# fp1.net
KiCad netlist of a schematic drawn in EAGLE
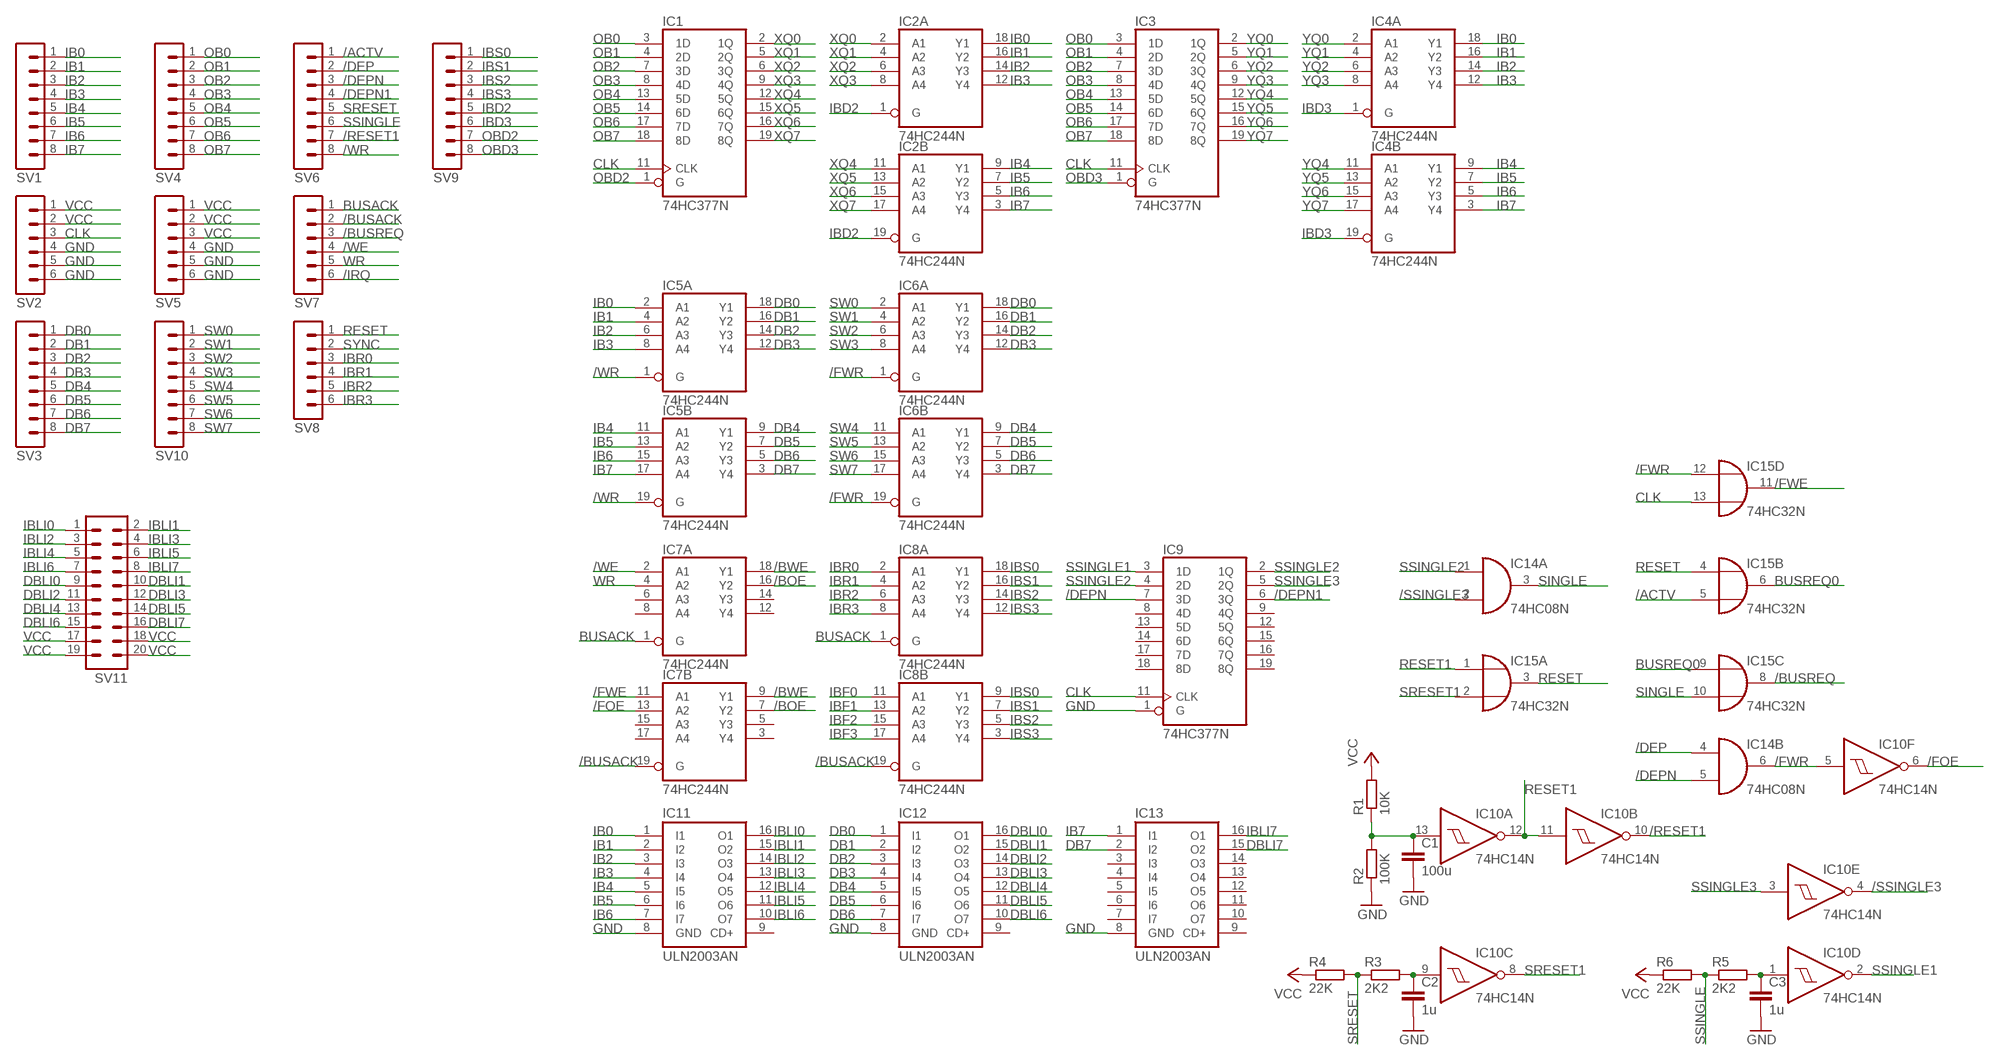
[diagram p0: schematic, sheet 1]

(export (version "E")
  (design (tool "Eeschema 10.0.6"))
  (components
    (comp (ref "C1")
      (value "100u")
      (footprint "eagle-import:C025-024X044")
      (libsource (lib "eagle-import") (part "C-EU025-024X044"))
    )
    (comp (ref "C2")
      (value "1u")
      (footprint "eagle-import:C025-024X044")
      (libsource (lib "eagle-import") (part "C-EU025-024X044"))
    )
    (comp (ref "C3")
      (value "1u")
      (footprint "eagle-import:C025-024X044")
      (libsource (lib "eagle-import") (part "C-EU025-024X044"))
    )
    (comp (ref "IC1")
      (value "74HC377N")
      (footprint "eagle-import:DIL20")
      (libsource (lib "eagle-import") (part "74377NHC"))
    )
    (comp (ref "IC2")
      (value "74HC244N")
      (footprint "eagle-import:DIL20")
      (libsource (lib "eagle-import") (part "74244NHC"))
    )
    (comp (ref "IC3")
      (value "74HC377N")
      (footprint "eagle-import:DIL20")
      (libsource (lib "eagle-import") (part "74377NHC"))
    )
    (comp (ref "IC4")
      (value "74HC244N")
      (footprint "eagle-import:DIL20")
      (libsource (lib "eagle-import") (part "74244NHC"))
    )
    (comp (ref "IC5")
      (value "74HC244N")
      (footprint "eagle-import:DIL20")
      (libsource (lib "eagle-import") (part "74244NHC"))
    )
    (comp (ref "IC6")
      (value "74HC244N")
      (footprint "eagle-import:DIL20")
      (libsource (lib "eagle-import") (part "74244NHC"))
    )
    (comp (ref "IC7")
      (value "74HC244N")
      (footprint "eagle-import:DIL20")
      (libsource (lib "eagle-import") (part "74244NHC"))
    )
    (comp (ref "IC8")
      (value "74HC244N")
      (footprint "eagle-import:DIL20")
      (libsource (lib "eagle-import") (part "74244NHC"))
    )
    (comp (ref "IC9")
      (value "74HC377N")
      (footprint "eagle-import:DIL20")
      (libsource (lib "eagle-import") (part "74377NHC"))
    )
    (comp (ref "IC10")
      (value "74HC14N")
      (footprint "eagle-import:DIL14")
      (libsource (lib "eagle-import") (part "7414NHC"))
    )
    (comp (ref "IC11")
      (value "ULN2003AN")
      (footprint "eagle-import:DIL16")
      (libsource (lib "eagle-import") (part "ULN2003AN"))
    )
    (comp (ref "IC12")
      (value "ULN2003AN")
      (footprint "eagle-import:DIL16")
      (libsource (lib "eagle-import") (part "ULN2003AN"))
    )
    (comp (ref "IC13")
      (value "ULN2003AN")
      (footprint "eagle-import:DIL16")
      (libsource (lib "eagle-import") (part "ULN2003AN"))
    )
    (comp (ref "IC14")
      (value "74HC08N")
      (footprint "eagle-import:DIL14")
      (libsource (lib "eagle-import") (part "7408NHC"))
    )
    (comp (ref "IC15")
      (value "74HC32N")
      (footprint "eagle-import:DIL14")
      (libsource (lib "eagle-import") (part "7432NHC"))
    )
    (comp (ref "R1")
      (value "10K")
      (footprint "eagle-import:0207_7")
      (libsource (lib "eagle-import") (part "R-EU_0207/7"))
    )
    (comp (ref "R2")
      (value "100K")
      (footprint "eagle-import:0207_7")
      (libsource (lib "eagle-import") (part "R-EU_0207/7"))
    )
    (comp (ref "R3")
      (value "2K2")
      (footprint "eagle-import:0207_7")
      (libsource (lib "eagle-import") (part "R-EU_0207/7"))
    )
    (comp (ref "R4")
      (value "22K")
      (footprint "eagle-import:0207_7")
      (libsource (lib "eagle-import") (part "R-EU_0207/7"))
    )
    (comp (ref "R5")
      (value "2K2")
      (footprint "eagle-import:0207_7")
      (libsource (lib "eagle-import") (part "R-EU_0207/7"))
    )
    (comp (ref "R6")
      (value "22K")
      (footprint "eagle-import:0207_7")
      (libsource (lib "eagle-import") (part "R-EU_0207/7"))
    )
    (comp (ref "SV1")
      (value "MA08-1")
      (footprint "eagle-import:MA08-1")
      (libsource (lib "eagle-import") (part "MA08-1"))
    )
    (comp (ref "SV2")
      (value "MA06-1")
      (footprint "eagle-import:MA06-1")
      (libsource (lib "eagle-import") (part "MA06-1"))
    )
    (comp (ref "SV3")
      (value "MA08-1")
      (footprint "eagle-import:MA08-1")
      (libsource (lib "eagle-import") (part "MA08-1"))
    )
    (comp (ref "SV4")
      (value "MA08-1")
      (footprint "eagle-import:MA08-1")
      (libsource (lib "eagle-import") (part "MA08-1"))
    )
    (comp (ref "SV5")
      (value "MA06-1")
      (footprint "eagle-import:MA06-1")
      (libsource (lib "eagle-import") (part "MA06-1"))
    )
    (comp (ref "SV6")
      (value "MA08-1")
      (footprint "eagle-import:MA08-1")
      (libsource (lib "eagle-import") (part "MA08-1"))
    )
    (comp (ref "SV7")
      (value "MA06-1")
      (footprint "eagle-import:MA06-1")
      (libsource (lib "eagle-import") (part "MA06-1"))
    )
    (comp (ref "SV8")
      (value "MA06-1")
      (footprint "eagle-import:MA06-1")
      (libsource (lib "eagle-import") (part "MA06-1"))
    )
    (comp (ref "SV9")
      (value "MA08-1")
      (footprint "eagle-import:MA08-1")
      (libsource (lib "eagle-import") (part "MA08-1"))
    )
    (comp (ref "SV10")
      (value "MA08-1")
      (footprint "eagle-import:MA08-1")
      (libsource (lib "eagle-import") (part "MA08-1"))
    )
    (comp (ref "SV11")
      (value "MA10-2")
      (footprint "eagle-import:MA10-2")
      (libsource (lib "eagle-import") (part "MA10-2"))
    )
  )
  (nets
    (net (code "1") (name "/BUSACK") (class "Default")
      (node (ref "IC7") (pin "1") (pinfunction "G_1") (pintype "input"))
      (node (ref "IC8") (pin "1") (pinfunction "G_1") (pintype "input"))
      (node (ref "SV7") (pin "1") (pinfunction "1_1") (pintype "passive"))
    )
    (net (code "2") (name "/BUSREQ0") (class "Default")
      (node (ref "IC15") (pin "6") (pinfunction "O_6") (pintype "output"))
      (node (ref "IC15") (pin "9") (pinfunction "I0_9") (pintype "input"))
    )
    (net (code "3") (name "/CLK") (class "Default")
      (node (ref "IC1") (pin "11") (pinfunction "CLK_11") (pintype "input"))
      (node (ref "IC15") (pin "13") (pinfunction "I1_13") (pintype "input"))
      (node (ref "IC3") (pin "11") (pinfunction "CLK_11") (pintype "input"))
      (node (ref "IC9") (pin "11") (pinfunction "CLK_11") (pintype "input"))
      (node (ref "SV2") (pin "3") (pinfunction "3_3") (pintype "passive"))
    )
    (net (code "4") (name "/DB0") (class "Default")
      (node (ref "IC12") (pin "1") (pinfunction "I1_1") (pintype "input"))
      (node (ref "IC5") (pin "18") (pinfunction "Y1_18") (pintype "tri_state"))
      (node (ref "IC6") (pin "18") (pinfunction "Y1_18") (pintype "tri_state"))
      (node (ref "SV3") (pin "1") (pinfunction "1_1") (pintype "passive"))
    )
    (net (code "5") (name "/DB1") (class "Default")
      (node (ref "IC12") (pin "2") (pinfunction "I2_2") (pintype "input"))
      (node (ref "IC5") (pin "16") (pinfunction "Y2_16") (pintype "tri_state"))
      (node (ref "IC6") (pin "16") (pinfunction "Y2_16") (pintype "tri_state"))
      (node (ref "SV3") (pin "2") (pinfunction "2_2") (pintype "passive"))
    )
    (net (code "6") (name "/DB2") (class "Default")
      (node (ref "IC12") (pin "3") (pinfunction "I3_3") (pintype "input"))
      (node (ref "IC5") (pin "14") (pinfunction "Y3_14") (pintype "tri_state"))
      (node (ref "IC6") (pin "14") (pinfunction "Y3_14") (pintype "tri_state"))
      (node (ref "SV3") (pin "3") (pinfunction "3_3") (pintype "passive"))
    )
    (net (code "7") (name "/DB3") (class "Default")
      (node (ref "IC12") (pin "4") (pinfunction "I4_4") (pintype "input"))
      (node (ref "IC5") (pin "12") (pinfunction "Y4_12") (pintype "tri_state"))
      (node (ref "IC6") (pin "12") (pinfunction "Y4_12") (pintype "tri_state"))
      (node (ref "SV3") (pin "4") (pinfunction "4_4") (pintype "passive"))
    )
    (net (code "8") (name "/DB4") (class "Default")
      (node (ref "IC12") (pin "5") (pinfunction "I5_5") (pintype "input"))
      (node (ref "IC5") (pin "9") (pinfunction "Y1_9") (pintype "tri_state"))
      (node (ref "IC6") (pin "9") (pinfunction "Y1_9") (pintype "tri_state"))
      (node (ref "SV3") (pin "5") (pinfunction "5_5") (pintype "passive"))
    )
    (net (code "9") (name "/DB5") (class "Default")
      (node (ref "IC12") (pin "6") (pinfunction "I6_6") (pintype "input"))
      (node (ref "IC5") (pin "7") (pinfunction "Y2_7") (pintype "tri_state"))
      (node (ref "IC6") (pin "7") (pinfunction "Y2_7") (pintype "tri_state"))
      (node (ref "SV3") (pin "6") (pinfunction "6_6") (pintype "passive"))
    )
    (net (code "10") (name "/DB6") (class "Default")
      (node (ref "IC12") (pin "7") (pinfunction "I7_7") (pintype "input"))
      (node (ref "IC5") (pin "5") (pinfunction "Y3_5") (pintype "tri_state"))
      (node (ref "IC6") (pin "5") (pinfunction "Y3_5") (pintype "tri_state"))
      (node (ref "SV3") (pin "7") (pinfunction "7_7") (pintype "passive"))
    )
    (net (code "11") (name "/DB7") (class "Default")
      (node (ref "IC13") (pin "2") (pinfunction "I2_2") (pintype "input"))
      (node (ref "IC5") (pin "3") (pinfunction "Y4_3") (pintype "tri_state"))
      (node (ref "IC6") (pin "3") (pinfunction "Y4_3") (pintype "tri_state"))
      (node (ref "SV3") (pin "8") (pinfunction "8_8") (pintype "passive"))
    )
    (net (code "12") (name "/DBLI0") (class "Default")
      (node (ref "IC12") (pin "16") (pinfunction "O1_16") (pintype "open_collector"))
      (node (ref "SV11") (pin "9") (pinfunction "9_9") (pintype "passive"))
    )
    (net (code "13") (name "/DBLI1") (class "Default")
      (node (ref "IC12") (pin "15") (pinfunction "O2_15") (pintype "open_collector"))
      (node (ref "SV11") (pin "10") (pinfunction "10_10") (pintype "passive"))
    )
    (net (code "14") (name "/DBLI2") (class "Default")
      (node (ref "IC12") (pin "14") (pinfunction "O3_14") (pintype "open_collector"))
      (node (ref "SV11") (pin "11") (pinfunction "11_11") (pintype "passive"))
    )
    (net (code "15") (name "/DBLI3") (class "Default")
      (node (ref "IC12") (pin "13") (pinfunction "O4_13") (pintype "open_collector"))
      (node (ref "SV11") (pin "12") (pinfunction "12_12") (pintype "passive"))
    )
    (net (code "16") (name "/DBLI4") (class "Default")
      (node (ref "IC12") (pin "12") (pinfunction "O5_12") (pintype "open_collector"))
      (node (ref "SV11") (pin "13") (pinfunction "13_13") (pintype "passive"))
    )
    (net (code "17") (name "/DBLI5") (class "Default")
      (node (ref "IC12") (pin "11") (pinfunction "O6_11") (pintype "open_collector"))
      (node (ref "SV11") (pin "14") (pinfunction "14_14") (pintype "passive"))
    )
    (net (code "18") (name "/DBLI6") (class "Default")
      (node (ref "IC12") (pin "10") (pinfunction "O7_10") (pintype "open_collector"))
      (node (ref "SV11") (pin "15") (pinfunction "15_15") (pintype "passive"))
    )
    (net (code "19") (name "/DBLI7") (class "Default")
      (node (ref "IC13") (pin "15") (pinfunction "O2_15") (pintype "open_collector"))
      (node (ref "SV11") (pin "16") (pinfunction "16_16") (pintype "passive"))
    )
    (net (code "20") (name "/IB0") (class "Default")
      (node (ref "IC11") (pin "1") (pinfunction "I1_1") (pintype "input"))
      (node (ref "IC2") (pin "18") (pinfunction "Y1_18") (pintype "tri_state"))
      (node (ref "IC4") (pin "18") (pinfunction "Y1_18") (pintype "tri_state"))
      (node (ref "IC5") (pin "2") (pinfunction "A1_2") (pintype "input"))
      (node (ref "SV1") (pin "1") (pinfunction "1_1") (pintype "passive"))
    )
    (net (code "21") (name "/IB1") (class "Default")
      (node (ref "IC11") (pin "2") (pinfunction "I2_2") (pintype "input"))
      (node (ref "IC2") (pin "16") (pinfunction "Y2_16") (pintype "tri_state"))
      (node (ref "IC4") (pin "16") (pinfunction "Y2_16") (pintype "tri_state"))
      (node (ref "IC5") (pin "4") (pinfunction "A2_4") (pintype "input"))
      (node (ref "SV1") (pin "2") (pinfunction "2_2") (pintype "passive"))
    )
    (net (code "22") (name "/IB2") (class "Default")
      (node (ref "IC11") (pin "3") (pinfunction "I3_3") (pintype "input"))
      (node (ref "IC2") (pin "14") (pinfunction "Y3_14") (pintype "tri_state"))
      (node (ref "IC4") (pin "14") (pinfunction "Y3_14") (pintype "tri_state"))
      (node (ref "IC5") (pin "6") (pinfunction "A3_6") (pintype "input"))
      (node (ref "SV1") (pin "3") (pinfunction "3_3") (pintype "passive"))
    )
    (net (code "23") (name "/IB3") (class "Default")
      (node (ref "IC11") (pin "4") (pinfunction "I4_4") (pintype "input"))
      (node (ref "IC2") (pin "12") (pinfunction "Y4_12") (pintype "tri_state"))
      (node (ref "IC4") (pin "12") (pinfunction "Y4_12") (pintype "tri_state"))
      (node (ref "IC5") (pin "8") (pinfunction "A4_8") (pintype "input"))
      (node (ref "SV1") (pin "4") (pinfunction "4_4") (pintype "passive"))
    )
    (net (code "24") (name "/IB4") (class "Default")
      (node (ref "IC11") (pin "5") (pinfunction "I5_5") (pintype "input"))
      (node (ref "IC2") (pin "9") (pinfunction "Y1_9") (pintype "tri_state"))
      (node (ref "IC4") (pin "9") (pinfunction "Y1_9") (pintype "tri_state"))
      (node (ref "IC5") (pin "11") (pinfunction "A1_11") (pintype "input"))
      (node (ref "SV1") (pin "5") (pinfunction "5_5") (pintype "passive"))
    )
    (net (code "25") (name "/IB5") (class "Default")
      (node (ref "IC11") (pin "6") (pinfunction "I6_6") (pintype "input"))
      (node (ref "IC2") (pin "7") (pinfunction "Y2_7") (pintype "tri_state"))
      (node (ref "IC4") (pin "7") (pinfunction "Y2_7") (pintype "tri_state"))
      (node (ref "IC5") (pin "13") (pinfunction "A2_13") (pintype "input"))
      (node (ref "SV1") (pin "6") (pinfunction "6_6") (pintype "passive"))
    )
    (net (code "26") (name "/IB6") (class "Default")
      (node (ref "IC11") (pin "7") (pinfunction "I7_7") (pintype "input"))
      (node (ref "IC2") (pin "5") (pinfunction "Y3_5") (pintype "tri_state"))
      (node (ref "IC4") (pin "5") (pinfunction "Y3_5") (pintype "tri_state"))
      (node (ref "IC5") (pin "15") (pinfunction "A3_15") (pintype "input"))
      (node (ref "SV1") (pin "7") (pinfunction "7_7") (pintype "passive"))
    )
    (net (code "27") (name "/IB7") (class "Default")
      (node (ref "IC13") (pin "1") (pinfunction "I1_1") (pintype "input"))
      (node (ref "IC2") (pin "3") (pinfunction "Y4_3") (pintype "tri_state"))
      (node (ref "IC4") (pin "3") (pinfunction "Y4_3") (pintype "tri_state"))
      (node (ref "IC5") (pin "17") (pinfunction "A4_17") (pintype "input"))
      (node (ref "SV1") (pin "8") (pinfunction "8_8") (pintype "passive"))
    )
    (net (code "28") (name "/IBD2") (class "Default")
      (node (ref "IC2") (pin "1") (pinfunction "G_1") (pintype "input"))
      (node (ref "IC2") (pin "19") (pinfunction "G_19") (pintype "input"))
      (node (ref "SV9") (pin "5") (pinfunction "5_5") (pintype "passive"))
    )
    (net (code "29") (name "/IBD3") (class "Default")
      (node (ref "IC4") (pin "1") (pinfunction "G_1") (pintype "input"))
      (node (ref "IC4") (pin "19") (pinfunction "G_19") (pintype "input"))
      (node (ref "SV9") (pin "6") (pinfunction "6_6") (pintype "passive"))
    )
    (net (code "30") (name "/IBF0") (class "Default")
      (node (ref "IC8") (pin "11") (pinfunction "A1_11") (pintype "input"))
    )
    (net (code "31") (name "/IBF1") (class "Default")
      (node (ref "IC8") (pin "13") (pinfunction "A2_13") (pintype "input"))
    )
    (net (code "32") (name "/IBF2") (class "Default")
      (node (ref "IC8") (pin "15") (pinfunction "A3_15") (pintype "input"))
    )
    (net (code "33") (name "/IBF3") (class "Default")
      (node (ref "IC8") (pin "17") (pinfunction "A4_17") (pintype "input"))
    )
    (net (code "34") (name "/IBLI0") (class "Default")
      (node (ref "IC11") (pin "16") (pinfunction "O1_16") (pintype "open_collector"))
      (node (ref "SV11") (pin "1") (pinfunction "1_1") (pintype "passive"))
    )
    (net (code "35") (name "/IBLI1") (class "Default")
      (node (ref "IC11") (pin "15") (pinfunction "O2_15") (pintype "open_collector"))
      (node (ref "SV11") (pin "2") (pinfunction "2_2") (pintype "passive"))
    )
    (net (code "36") (name "/IBLI2") (class "Default")
      (node (ref "IC11") (pin "14") (pinfunction "O3_14") (pintype "open_collector"))
      (node (ref "SV11") (pin "3") (pinfunction "3_3") (pintype "passive"))
    )
    (net (code "37") (name "/IBLI3") (class "Default")
      (node (ref "IC11") (pin "13") (pinfunction "O4_13") (pintype "open_collector"))
      (node (ref "SV11") (pin "4") (pinfunction "4_4") (pintype "passive"))
    )
    (net (code "38") (name "/IBLI4") (class "Default")
      (node (ref "IC11") (pin "12") (pinfunction "O5_12") (pintype "open_collector"))
      (node (ref "SV11") (pin "5") (pinfunction "5_5") (pintype "passive"))
    )
    (net (code "39") (name "/IBLI5") (class "Default")
      (node (ref "IC11") (pin "11") (pinfunction "O6_11") (pintype "open_collector"))
      (node (ref "SV11") (pin "6") (pinfunction "6_6") (pintype "passive"))
    )
    (net (code "40") (name "/IBLI6") (class "Default")
      (node (ref "IC11") (pin "10") (pinfunction "O7_10") (pintype "open_collector"))
      (node (ref "SV11") (pin "7") (pinfunction "7_7") (pintype "passive"))
    )
    (net (code "41") (name "/IBLI7") (class "Default")
      (node (ref "IC13") (pin "16") (pinfunction "O1_16") (pintype "open_collector"))
      (node (ref "SV11") (pin "8") (pinfunction "8_8") (pintype "passive"))
    )
    (net (code "42") (name "/IBR0") (class "Default")
      (node (ref "IC8") (pin "2") (pinfunction "A1_2") (pintype "input"))
      (node (ref "SV8") (pin "3") (pinfunction "3_3") (pintype "passive"))
    )
    (net (code "43") (name "/IBR1") (class "Default")
      (node (ref "IC8") (pin "4") (pinfunction "A2_4") (pintype "input"))
      (node (ref "SV8") (pin "4") (pinfunction "4_4") (pintype "passive"))
    )
    (net (code "44") (name "/IBR2") (class "Default")
      (node (ref "IC8") (pin "6") (pinfunction "A3_6") (pintype "input"))
      (node (ref "SV8") (pin "5") (pinfunction "5_5") (pintype "passive"))
    )
    (net (code "45") (name "/IBR3") (class "Default")
      (node (ref "IC8") (pin "8") (pinfunction "A4_8") (pintype "input"))
      (node (ref "SV8") (pin "6") (pinfunction "6_6") (pintype "passive"))
    )
    (net (code "46") (name "/IBS0") (class "Default")
      (node (ref "IC8") (pin "18") (pinfunction "Y1_18") (pintype "tri_state"))
      (node (ref "IC8") (pin "9") (pinfunction "Y1_9") (pintype "tri_state"))
      (node (ref "SV9") (pin "1") (pinfunction "1_1") (pintype "passive"))
    )
    (net (code "47") (name "/IBS1") (class "Default")
      (node (ref "IC8") (pin "16") (pinfunction "Y2_16") (pintype "tri_state"))
      (node (ref "IC8") (pin "7") (pinfunction "Y2_7") (pintype "tri_state"))
      (node (ref "SV9") (pin "2") (pinfunction "2_2") (pintype "passive"))
    )
    (net (code "48") (name "/IBS2") (class "Default")
      (node (ref "IC8") (pin "14") (pinfunction "Y3_14") (pintype "tri_state"))
      (node (ref "IC8") (pin "5") (pinfunction "Y3_5") (pintype "tri_state"))
      (node (ref "SV9") (pin "3") (pinfunction "3_3") (pintype "passive"))
    )
    (net (code "49") (name "/IBS3") (class "Default")
      (node (ref "IC8") (pin "12") (pinfunction "Y4_12") (pintype "tri_state"))
      (node (ref "IC8") (pin "3") (pinfunction "Y4_3") (pintype "tri_state"))
      (node (ref "SV9") (pin "4") (pinfunction "4_4") (pintype "passive"))
    )
    (net (code "50") (name "/OB0") (class "Default")
      (node (ref "IC1") (pin "3") (pinfunction "1D_3") (pintype "input"))
      (node (ref "IC3") (pin "3") (pinfunction "1D_3") (pintype "input"))
      (node (ref "SV4") (pin "1") (pinfunction "1_1") (pintype "passive"))
    )
    (net (code "51") (name "/OB1") (class "Default")
      (node (ref "IC1") (pin "4") (pinfunction "2D_4") (pintype "input"))
      (node (ref "IC3") (pin "4") (pinfunction "2D_4") (pintype "input"))
      (node (ref "SV4") (pin "2") (pinfunction "2_2") (pintype "passive"))
    )
    (net (code "52") (name "/OB2") (class "Default")
      (node (ref "IC1") (pin "7") (pinfunction "3D_7") (pintype "input"))
      (node (ref "IC3") (pin "7") (pinfunction "3D_7") (pintype "input"))
      (node (ref "SV4") (pin "3") (pinfunction "3_3") (pintype "passive"))
    )
    (net (code "53") (name "/OB3") (class "Default")
      (node (ref "IC1") (pin "8") (pinfunction "4D_8") (pintype "input"))
      (node (ref "IC3") (pin "8") (pinfunction "4D_8") (pintype "input"))
      (node (ref "SV4") (pin "4") (pinfunction "4_4") (pintype "passive"))
    )
    (net (code "54") (name "/OB4") (class "Default")
      (node (ref "IC1") (pin "13") (pinfunction "5D_13") (pintype "input"))
      (node (ref "IC3") (pin "13") (pinfunction "5D_13") (pintype "input"))
      (node (ref "SV4") (pin "5") (pinfunction "5_5") (pintype "passive"))
    )
    (net (code "55") (name "/OB5") (class "Default")
      (node (ref "IC1") (pin "14") (pinfunction "6D_14") (pintype "input"))
      (node (ref "IC3") (pin "14") (pinfunction "6D_14") (pintype "input"))
      (node (ref "SV4") (pin "6") (pinfunction "6_6") (pintype "passive"))
    )
    (net (code "56") (name "/OB6") (class "Default")
      (node (ref "IC1") (pin "17") (pinfunction "7D_17") (pintype "input"))
      (node (ref "IC3") (pin "17") (pinfunction "7D_17") (pintype "input"))
      (node (ref "SV4") (pin "7") (pinfunction "7_7") (pintype "passive"))
    )
    (net (code "57") (name "/OB7") (class "Default")
      (node (ref "IC1") (pin "18") (pinfunction "8D_18") (pintype "input"))
      (node (ref "IC3") (pin "18") (pinfunction "8D_18") (pintype "input"))
      (node (ref "SV4") (pin "8") (pinfunction "8_8") (pintype "passive"))
    )
    (net (code "58") (name "/OBD2") (class "Default")
      (node (ref "IC1") (pin "1") (pinfunction "G_1") (pintype "input"))
      (node (ref "SV9") (pin "7") (pinfunction "7_7") (pintype "passive"))
    )
    (net (code "59") (name "/OBD3") (class "Default")
      (node (ref "IC3") (pin "1") (pinfunction "G_1") (pintype "input"))
      (node (ref "SV9") (pin "8") (pinfunction "8_8") (pintype "passive"))
    )
    (net (code "60") (name "/RESET") (class "Default")
      (node (ref "IC15") (pin "3") (pinfunction "O_3") (pintype "output"))
      (node (ref "IC15") (pin "4") (pinfunction "I0_4") (pintype "input"))
      (node (ref "SV8") (pin "1") (pinfunction "1_1") (pintype "passive"))
    )
    (net (code "61") (name "/RESET1") (class "Default")
      (node (ref "IC10") (pin "11") (pinfunction "I_11") (pintype "input"))
      (node (ref "IC10") (pin "12") (pinfunction "O_12") (pintype "output"))
      (node (ref "IC15") (pin "1") (pinfunction "I0_1") (pintype "input"))
    )
    (net (code "62") (name "/SINGLE") (class "Default")
      (node (ref "IC14") (pin "3") (pinfunction "O_3") (pintype "output"))
      (node (ref "IC15") (pin "10") (pinfunction "I1_10") (pintype "input"))
    )
    (net (code "63") (name "/SRESET") (class "Default")
      (node (ref "R3") (pin "1") (pinfunction "1_1") (pintype "passive"))
      (node (ref "R4") (pin "2") (pinfunction "2_2") (pintype "passive"))
      (node (ref "SV6") (pin "5") (pinfunction "5_5") (pintype "passive"))
    )
    (net (code "64") (name "/SRESET1") (class "Default")
      (node (ref "IC10") (pin "8") (pinfunction "O_8") (pintype "output"))
      (node (ref "IC15") (pin "2") (pinfunction "I1_2") (pintype "input"))
    )
    (net (code "65") (name "/SSINGLE") (class "Default")
      (node (ref "R5") (pin "1") (pinfunction "1_1") (pintype "passive"))
      (node (ref "R6") (pin "2") (pinfunction "2_2") (pintype "passive"))
      (node (ref "SV6") (pin "6") (pinfunction "6_6") (pintype "passive"))
    )
    (net (code "66") (name "/SSINGLE1") (class "Default")
      (node (ref "IC10") (pin "2") (pinfunction "O_2") (pintype "output"))
      (node (ref "IC9") (pin "3") (pinfunction "1D_3") (pintype "input"))
    )
    (net (code "67") (name "/SSINGLE2") (class "Default")
      (node (ref "IC14") (pin "1") (pinfunction "I0_1") (pintype "input"))
      (node (ref "IC9") (pin "2") (pinfunction "1Q_2") (pintype "output"))
      (node (ref "IC9") (pin "4") (pinfunction "2D_4") (pintype "input"))
    )
    (net (code "68") (name "/SSINGLE3") (class "Default")
      (node (ref "IC10") (pin "3") (pinfunction "I_3") (pintype "input"))
      (node (ref "IC9") (pin "5") (pinfunction "2Q_5") (pintype "output"))
    )
    (net (code "69") (name "/SW0") (class "Default")
      (node (ref "IC6") (pin "2") (pinfunction "A1_2") (pintype "input"))
      (node (ref "SV10") (pin "1") (pinfunction "1_1") (pintype "passive"))
    )
    (net (code "70") (name "/SW1") (class "Default")
      (node (ref "IC6") (pin "4") (pinfunction "A2_4") (pintype "input"))
      (node (ref "SV10") (pin "2") (pinfunction "2_2") (pintype "passive"))
    )
    (net (code "71") (name "/SW2") (class "Default")
      (node (ref "IC6") (pin "6") (pinfunction "A3_6") (pintype "input"))
      (node (ref "SV10") (pin "3") (pinfunction "3_3") (pintype "passive"))
    )
    (net (code "72") (name "/SW3") (class "Default")
      (node (ref "IC6") (pin "8") (pinfunction "A4_8") (pintype "input"))
      (node (ref "SV10") (pin "4") (pinfunction "4_4") (pintype "passive"))
    )
    (net (code "73") (name "/SW4") (class "Default")
      (node (ref "IC6") (pin "11") (pinfunction "A1_11") (pintype "input"))
      (node (ref "SV10") (pin "5") (pinfunction "5_5") (pintype "passive"))
    )
    (net (code "74") (name "/SW5") (class "Default")
      (node (ref "IC6") (pin "13") (pinfunction "A2_13") (pintype "input"))
      (node (ref "SV10") (pin "6") (pinfunction "6_6") (pintype "passive"))
    )
    (net (code "75") (name "/SW6") (class "Default")
      (node (ref "IC6") (pin "15") (pinfunction "A3_15") (pintype "input"))
      (node (ref "SV10") (pin "7") (pinfunction "7_7") (pintype "passive"))
    )
    (net (code "76") (name "/SW7") (class "Default")
      (node (ref "IC6") (pin "17") (pinfunction "A4_17") (pintype "input"))
      (node (ref "SV10") (pin "8") (pinfunction "8_8") (pintype "passive"))
    )
    (net (code "77") (name "/SYNC") (class "Default")
      (node (ref "SV8") (pin "2") (pinfunction "2_2") (pintype "passive"))
    )
    (net (code "78") (name "/WR") (class "Default")
      (node (ref "IC7") (pin "4") (pinfunction "A2_4") (pintype "input"))
      (node (ref "SV7") (pin "5") (pinfunction "5_5") (pintype "passive"))
    )
    (net (code "79") (name "/XQ0") (class "Default")
      (node (ref "IC1") (pin "2") (pinfunction "1Q_2") (pintype "output"))
      (node (ref "IC2") (pin "2") (pinfunction "A1_2") (pintype "input"))
    )
    (net (code "80") (name "/XQ1") (class "Default")
      (node (ref "IC1") (pin "5") (pinfunction "2Q_5") (pintype "output"))
      (node (ref "IC2") (pin "4") (pinfunction "A2_4") (pintype "input"))
    )
    (net (code "81") (name "/XQ2") (class "Default")
      (node (ref "IC1") (pin "6") (pinfunction "3Q_6") (pintype "output"))
      (node (ref "IC2") (pin "6") (pinfunction "A3_6") (pintype "input"))
    )
    (net (code "82") (name "/XQ3") (class "Default")
      (node (ref "IC1") (pin "9") (pinfunction "4Q_9") (pintype "output"))
      (node (ref "IC2") (pin "8") (pinfunction "A4_8") (pintype "input"))
    )
    (net (code "83") (name "/XQ4") (class "Default")
      (node (ref "IC1") (pin "12") (pinfunction "5Q_12") (pintype "output"))
      (node (ref "IC2") (pin "11") (pinfunction "A1_11") (pintype "input"))
    )
    (net (code "84") (name "/XQ5") (class "Default")
      (node (ref "IC1") (pin "15") (pinfunction "6Q_15") (pintype "output"))
      (node (ref "IC2") (pin "13") (pinfunction "A2_13") (pintype "input"))
    )
    (net (code "85") (name "/XQ6") (class "Default")
      (node (ref "IC1") (pin "16") (pinfunction "7Q_16") (pintype "output"))
      (node (ref "IC2") (pin "15") (pinfunction "A3_15") (pintype "input"))
    )
    (net (code "86") (name "/XQ7") (class "Default")
      (node (ref "IC1") (pin "19") (pinfunction "8Q_19") (pintype "output"))
      (node (ref "IC2") (pin "17") (pinfunction "A4_17") (pintype "input"))
    )
    (net (code "87") (name "/YQ0") (class "Default")
      (node (ref "IC3") (pin "2") (pinfunction "1Q_2") (pintype "output"))
      (node (ref "IC4") (pin "2") (pinfunction "A1_2") (pintype "input"))
    )
    (net (code "88") (name "/YQ1") (class "Default")
      (node (ref "IC3") (pin "5") (pinfunction "2Q_5") (pintype "output"))
      (node (ref "IC4") (pin "4") (pinfunction "A2_4") (pintype "input"))
    )
    (net (code "89") (name "/YQ2") (class "Default")
      (node (ref "IC3") (pin "6") (pinfunction "3Q_6") (pintype "output"))
      (node (ref "IC4") (pin "6") (pinfunction "A3_6") (pintype "input"))
    )
    (net (code "90") (name "/YQ3") (class "Default")
      (node (ref "IC3") (pin "9") (pinfunction "4Q_9") (pintype "output"))
      (node (ref "IC4") (pin "8") (pinfunction "A4_8") (pintype "input"))
    )
    (net (code "91") (name "/YQ4") (class "Default")
      (node (ref "IC3") (pin "12") (pinfunction "5Q_12") (pintype "output"))
      (node (ref "IC4") (pin "11") (pinfunction "A1_11") (pintype "input"))
    )
    (net (code "92") (name "/YQ5") (class "Default")
      (node (ref "IC3") (pin "15") (pinfunction "6Q_15") (pintype "output"))
      (node (ref "IC4") (pin "13") (pinfunction "A2_13") (pintype "input"))
    )
    (net (code "93") (name "/YQ6") (class "Default")
      (node (ref "IC3") (pin "16") (pinfunction "7Q_16") (pintype "output"))
      (node (ref "IC4") (pin "15") (pinfunction "A3_15") (pintype "input"))
    )
    (net (code "94") (name "/YQ7") (class "Default")
      (node (ref "IC3") (pin "19") (pinfunction "8Q_19") (pintype "output"))
      (node (ref "IC4") (pin "17") (pinfunction "A4_17") (pintype "input"))
    )
    (net (code "95") (name "/{slash}ACTV") (class "Default")
      (node (ref "IC15") (pin "5") (pinfunction "I1_5") (pintype "input"))
      (node (ref "SV6") (pin "1") (pinfunction "1_1") (pintype "passive"))
    )
    (net (code "96") (name "/{slash}BOE") (class "Default")
      (node (ref "IC7") (pin "16") (pinfunction "Y2_16") (pintype "tri_state"))
      (node (ref "IC7") (pin "7") (pinfunction "Y2_7") (pintype "tri_state"))
    )
    (net (code "97") (name "/{slash}BUSACK") (class "Default")
      (node (ref "IC7") (pin "19") (pinfunction "G_19") (pintype "input"))
      (node (ref "IC8") (pin "19") (pinfunction "G_19") (pintype "input"))
      (node (ref "SV7") (pin "2") (pinfunction "2_2") (pintype "passive"))
    )
    (net (code "98") (name "/{slash}BUSREQ") (class "Default")
      (node (ref "IC15") (pin "8") (pinfunction "O_8") (pintype "output"))
      (node (ref "SV7") (pin "3") (pinfunction "3_3") (pintype "passive"))
    )
    (net (code "99") (name "/{slash}BWE") (class "Default")
      (node (ref "IC7") (pin "18") (pinfunction "Y1_18") (pintype "tri_state"))
      (node (ref "IC7") (pin "9") (pinfunction "Y1_9") (pintype "tri_state"))
    )
    (net (code "100") (name "/{slash}DEP") (class "Default")
      (node (ref "IC14") (pin "4") (pinfunction "I0_4") (pintype "input"))
      (node (ref "SV6") (pin "2") (pinfunction "2_2") (pintype "passive"))
    )
    (net (code "101") (name "/{slash}DEPN") (class "Default")
      (node (ref "IC14") (pin "5") (pinfunction "I1_5") (pintype "input"))
      (node (ref "IC9") (pin "7") (pinfunction "3D_7") (pintype "input"))
      (node (ref "SV6") (pin "3") (pinfunction "3_3") (pintype "passive"))
    )
    (net (code "102") (name "/{slash}DEPN1") (class "Default")
      (node (ref "IC9") (pin "6") (pinfunction "3Q_6") (pintype "output"))
      (node (ref "SV6") (pin "4") (pinfunction "4_4") (pintype "passive"))
    )
    (net (code "103") (name "/{slash}FOE") (class "Default")
      (node (ref "IC10") (pin "6") (pinfunction "O_6") (pintype "output"))
      (node (ref "IC7") (pin "13") (pinfunction "A2_13") (pintype "input"))
    )
    (net (code "104") (name "/{slash}FWE") (class "Default")
      (node (ref "IC15") (pin "11") (pinfunction "O_11") (pintype "output"))
      (node (ref "IC7") (pin "11") (pinfunction "A1_11") (pintype "input"))
    )
    (net (code "105") (name "/{slash}FWR") (class "Default")
      (node (ref "IC10") (pin "5") (pinfunction "I_5") (pintype "input"))
      (node (ref "IC14") (pin "6") (pinfunction "O_6") (pintype "output"))
      (node (ref "IC15") (pin "12") (pinfunction "I0_12") (pintype "input"))
      (node (ref "IC6") (pin "1") (pinfunction "G_1") (pintype "input"))
      (node (ref "IC6") (pin "19") (pinfunction "G_19") (pintype "input"))
    )
    (net (code "106") (name "/{slash}IRQ") (class "Default")
      (node (ref "SV7") (pin "6") (pinfunction "6_6") (pintype "passive"))
    )
    (net (code "107") (name "/{slash}RESET1") (class "Default")
      (node (ref "IC10") (pin "10") (pinfunction "O_10") (pintype "output"))
      (node (ref "SV6") (pin "7") (pinfunction "7_7") (pintype "passive"))
    )
    (net (code "108") (name "/{slash}SSINGLE3") (class "Default")
      (node (ref "IC10") (pin "4") (pinfunction "O_4") (pintype "output"))
      (node (ref "IC14") (pin "2") (pinfunction "I1_2") (pintype "input"))
    )
    (net (code "109") (name "/{slash}WE") (class "Default")
      (node (ref "IC7") (pin "2") (pinfunction "A1_2") (pintype "input"))
      (node (ref "SV7") (pin "4") (pinfunction "4_4") (pintype "passive"))
    )
    (net (code "110") (name "/{slash}WR") (class "Default")
      (node (ref "IC5") (pin "1") (pinfunction "G_1") (pintype "input"))
      (node (ref "IC5") (pin "19") (pinfunction "G_19") (pintype "input"))
      (node (ref "SV6") (pin "8") (pinfunction "8_8") (pintype "passive"))
    )
    (net (code "111") (name "GND") (class "Default")
      (node (ref "C1") (pin "2") (pinfunction "2_2") (pintype "passive"))
      (node (ref "C2") (pin "2") (pinfunction "2_2") (pintype "passive"))
      (node (ref "C3") (pin "2") (pinfunction "2_2") (pintype "passive"))
      (node (ref "IC11") (pin "8") (pinfunction "GND_8") (pintype "power_in"))
      (node (ref "IC12") (pin "8") (pinfunction "GND_8") (pintype "power_in"))
      (node (ref "IC13") (pin "8") (pinfunction "GND_8") (pintype "power_in"))
      (node (ref "IC9") (pin "1") (pinfunction "G_1") (pintype "input"))
      (node (ref "R2") (pin "1") (pinfunction "1_1") (pintype "passive"))
      (node (ref "SV2") (pin "4") (pinfunction "4_4") (pintype "passive"))
      (node (ref "SV2") (pin "5") (pinfunction "5_5") (pintype "passive"))
      (node (ref "SV2") (pin "6") (pinfunction "6_6") (pintype "passive"))
      (node (ref "SV5") (pin "4") (pinfunction "4_4") (pintype "passive"))
      (node (ref "SV5") (pin "5") (pinfunction "5_5") (pintype "passive"))
      (node (ref "SV5") (pin "6") (pinfunction "6_6") (pintype "passive"))
    )
    (net (code "112") (name "Net-(IC10A-I)") (class "Default")
      (node (ref "C1") (pin "1") (pinfunction "1_1") (pintype "passive"))
      (node (ref "IC10") (pin "13") (pinfunction "I_13") (pintype "input"))
      (node (ref "R1") (pin "1") (pinfunction "1_1") (pintype "passive"))
      (node (ref "R2") (pin "2") (pinfunction "2_2") (pintype "passive"))
    )
    (net (code "113") (name "Net-(IC10C-I)") (class "Default")
      (node (ref "C2") (pin "1") (pinfunction "1_1") (pintype "passive"))
      (node (ref "IC10") (pin "9") (pinfunction "I_9") (pintype "input"))
      (node (ref "R3") (pin "2") (pinfunction "2_2") (pintype "passive"))
    )
    (net (code "114") (name "Net-(IC10D-I)") (class "Default")
      (node (ref "C3") (pin "1") (pinfunction "1_1") (pintype "passive"))
      (node (ref "IC10") (pin "1") (pinfunction "I_1") (pintype "input"))
      (node (ref "R5") (pin "2") (pinfunction "2_2") (pintype "passive"))
    )
    (net (code "115") (name "VCC") (class "Default")
      (node (ref "R1") (pin "2") (pinfunction "2_2") (pintype "passive"))
      (node (ref "R4") (pin "1") (pinfunction "1_1") (pintype "passive"))
      (node (ref "R6") (pin "1") (pinfunction "1_1") (pintype "passive"))
      (node (ref "SV11") (pin "17") (pinfunction "17_17") (pintype "passive"))
      (node (ref "SV11") (pin "18") (pinfunction "18_18") (pintype "passive"))
      (node (ref "SV11") (pin "19") (pinfunction "19_19") (pintype "passive"))
      (node (ref "SV11") (pin "20") (pinfunction "20_20") (pintype "passive"))
      (node (ref "SV2") (pin "1") (pinfunction "1_1") (pintype "passive"))
      (node (ref "SV2") (pin "2") (pinfunction "2_2") (pintype "passive"))
      (node (ref "SV5") (pin "1") (pinfunction "1_1") (pintype "passive"))
      (node (ref "SV5") (pin "2") (pinfunction "2_2") (pintype "passive"))
      (node (ref "SV5") (pin "3") (pinfunction "3_3") (pintype "passive"))
    )
    (net (code "116") (name "unconnected-(IC7A-A3-Pad6)") (class "Default")
      (node (ref "IC7") (pin "6") (pinfunction "A3_6") (pintype "input"))
    )
    (net (code "117") (name "unconnected-(IC7A-A4-Pad8)") (class "Default")
      (node (ref "IC7") (pin "8") (pinfunction "A4_8") (pintype "input"))
    )
    (net (code "118") (name "unconnected-(IC7A-Y3-Pad14)") (class "Default")
      (node (ref "IC7") (pin "14") (pinfunction "Y3_14") (pintype "tri_state"))
    )
    (net (code "119") (name "unconnected-(IC7A-Y4-Pad12)") (class "Default")
      (node (ref "IC7") (pin "12") (pinfunction "Y4_12") (pintype "tri_state"))
    )
    (net (code "120") (name "unconnected-(IC7B-A3-Pad15)") (class "Default")
      (node (ref "IC7") (pin "15") (pinfunction "A3_15") (pintype "input"))
    )
    (net (code "121") (name "unconnected-(IC7B-A4-Pad17)") (class "Default")
      (node (ref "IC7") (pin "17") (pinfunction "A4_17") (pintype "input"))
    )
    (net (code "122") (name "unconnected-(IC7B-Y3-Pad5)") (class "Default")
      (node (ref "IC7") (pin "5") (pinfunction "Y3_5") (pintype "tri_state"))
    )
    (net (code "123") (name "unconnected-(IC7B-Y4-Pad3)") (class "Default")
      (node (ref "IC7") (pin "3") (pinfunction "Y4_3") (pintype "tri_state"))
    )
    (net (code "124") (name "unconnected-(IC9A-4D-Pad8)") (class "Default")
      (node (ref "IC9") (pin "8") (pinfunction "4D_8") (pintype "input"))
    )
    (net (code "125") (name "unconnected-(IC9A-4Q-Pad9)") (class "Default")
      (node (ref "IC9") (pin "9") (pinfunction "4Q_9") (pintype "output"))
    )
    (net (code "126") (name "unconnected-(IC9A-5D-Pad13)") (class "Default")
      (node (ref "IC9") (pin "13") (pinfunction "5D_13") (pintype "input"))
    )
    (net (code "127") (name "unconnected-(IC9A-5Q-Pad12)") (class "Default")
      (node (ref "IC9") (pin "12") (pinfunction "5Q_12") (pintype "output"))
    )
    (net (code "128") (name "unconnected-(IC9A-6D-Pad14)") (class "Default")
      (node (ref "IC9") (pin "14") (pinfunction "6D_14") (pintype "input"))
    )
    (net (code "129") (name "unconnected-(IC9A-6Q-Pad15)") (class "Default")
      (node (ref "IC9") (pin "15") (pinfunction "6Q_15") (pintype "output"))
    )
    (net (code "130") (name "unconnected-(IC9A-7D-Pad17)") (class "Default")
      (node (ref "IC9") (pin "17") (pinfunction "7D_17") (pintype "input"))
    )
    (net (code "131") (name "unconnected-(IC9A-7Q-Pad16)") (class "Default")
      (node (ref "IC9") (pin "16") (pinfunction "7Q_16") (pintype "output"))
    )
    (net (code "132") (name "unconnected-(IC9A-8D-Pad18)") (class "Default")
      (node (ref "IC9") (pin "18") (pinfunction "8D_18") (pintype "input"))
    )
    (net (code "133") (name "unconnected-(IC9A-8Q-Pad19)") (class "Default")
      (node (ref "IC9") (pin "19") (pinfunction "8Q_19") (pintype "output"))
    )
    (net (code "134") (name "unconnected-(IC11-CD+-Pad9)") (class "Default")
      (node (ref "IC11") (pin "9") (pinfunction "CD+_9") (pintype "passive"))
    )
    (net (code "135") (name "unconnected-(IC12-CD+-Pad9)") (class "Default")
      (node (ref "IC12") (pin "9") (pinfunction "CD+_9") (pintype "passive"))
    )
    (net (code "136") (name "unconnected-(IC13-CD+-Pad9)") (class "Default")
      (node (ref "IC13") (pin "9") (pinfunction "CD+_9") (pintype "passive"))
    )
    (net (code "137") (name "unconnected-(IC13-I3-Pad3)") (class "Default")
      (node (ref "IC13") (pin "3") (pinfunction "I3_3") (pintype "input"))
    )
    (net (code "138") (name "unconnected-(IC13-I4-Pad4)") (class "Default")
      (node (ref "IC13") (pin "4") (pinfunction "I4_4") (pintype "input"))
    )
    (net (code "139") (name "unconnected-(IC13-I5-Pad5)") (class "Default")
      (node (ref "IC13") (pin "5") (pinfunction "I5_5") (pintype "input"))
    )
    (net (code "140") (name "unconnected-(IC13-I6-Pad6)") (class "Default")
      (node (ref "IC13") (pin "6") (pinfunction "I6_6") (pintype "input"))
    )
    (net (code "141") (name "unconnected-(IC13-I7-Pad7)") (class "Default")
      (node (ref "IC13") (pin "7") (pinfunction "I7_7") (pintype "input"))
    )
    (net (code "142") (name "unconnected-(IC13-O3-Pad14)") (class "Default")
      (node (ref "IC13") (pin "14") (pinfunction "O3_14") (pintype "open_collector"))
    )
    (net (code "143") (name "unconnected-(IC13-O4-Pad13)") (class "Default")
      (node (ref "IC13") (pin "13") (pinfunction "O4_13") (pintype "open_collector"))
    )
    (net (code "144") (name "unconnected-(IC13-O5-Pad12)") (class "Default")
      (node (ref "IC13") (pin "12") (pinfunction "O5_12") (pintype "open_collector"))
    )
    (net (code "145") (name "unconnected-(IC13-O6-Pad11)") (class "Default")
      (node (ref "IC13") (pin "11") (pinfunction "O6_11") (pintype "open_collector"))
    )
    (net (code "146") (name "unconnected-(IC13-O7-Pad10)") (class "Default")
      (node (ref "IC13") (pin "10") (pinfunction "O7_10") (pintype "open_collector"))
    )
  )
)
